# Neutral_White_LEDs.net
KiCad netlist of a schematic drawn in Altium Designer
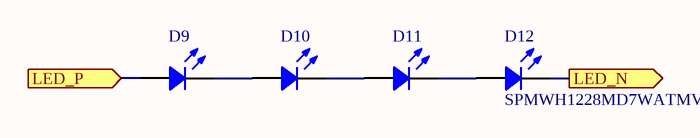
[diagram p0: Neutral White LEDs.SchDoc]

(export (version "E")
  (design (tool "Eeschema 10.0.6"))
  (components
    (comp (ref "D9")
      (value "SPMWH1228MD7WATMVL")
      (footprint "SAMSUNG LM281BPLUS")
      (description "LED")
      (fields (field (name "MANUFACTURER") "Samsung Semiconductor, Inc."))
      (libsource (lib "altiumlibrary.com") (part "LED A-C"))
    )
    (comp (ref "D10")
      (value "SPMWH1228MD7WATMVL")
      (footprint "SAMSUNG LM281BPLUS")
      (description "LED")
      (fields (field (name "MANUFACTURER") "Samsung Semiconductor, Inc."))
      (libsource (lib "altiumlibrary.com") (part "LED A-C"))
    )
    (comp (ref "D11")
      (value "SPMWH1228MD7WATMVL")
      (footprint "SAMSUNG LM281BPLUS")
      (description "LED")
      (fields (field (name "MANUFACTURER") "Samsung Semiconductor, Inc."))
      (libsource (lib "altiumlibrary.com") (part "LED A-C"))
    )
    (comp (ref "D12")
      (value "SPMWH1228MD7WATMVL")
      (footprint "SAMSUNG LM281BPLUS")
      (description "LED")
      (fields (field (name "MANUFACTURER") "Samsung Semiconductor, Inc."))
      (libsource (lib "altiumlibrary.com") (part "LED A-C"))
    )
  )
  (nets
    (net (code "1") (name "/LED_N") (class "Default")
      (node (ref "D12") (pin "C") (pinfunction "C_C") (pintype "passive"))
    )
    (net (code "2") (name "/LED_P") (class "Default")
      (node (ref "D9") (pin "A") (pinfunction "A_A") (pintype "passive"))
    )
    (net (code "3") (name "Net-(D10-PadA)") (class "Default")
      (node (ref "D10") (pin "A") (pinfunction "A_A") (pintype "passive"))
      (node (ref "D9") (pin "C") (pinfunction "C_C") (pintype "passive"))
    )
    (net (code "4") (name "Net-(D10-PadC)") (class "Default")
      (node (ref "D10") (pin "C") (pinfunction "C_C") (pintype "passive"))
      (node (ref "D11") (pin "A") (pinfunction "A_A") (pintype "passive"))
    )
    (net (code "5") (name "Net-(D11-PadC)") (class "Default")
      (node (ref "D11") (pin "C") (pinfunction "C_C") (pintype "passive"))
      (node (ref "D12") (pin "A") (pinfunction "A_A") (pintype "passive"))
    )
  )
)
